# Outputs.net
KiCad netlist of a schematic drawn in Altium Designer
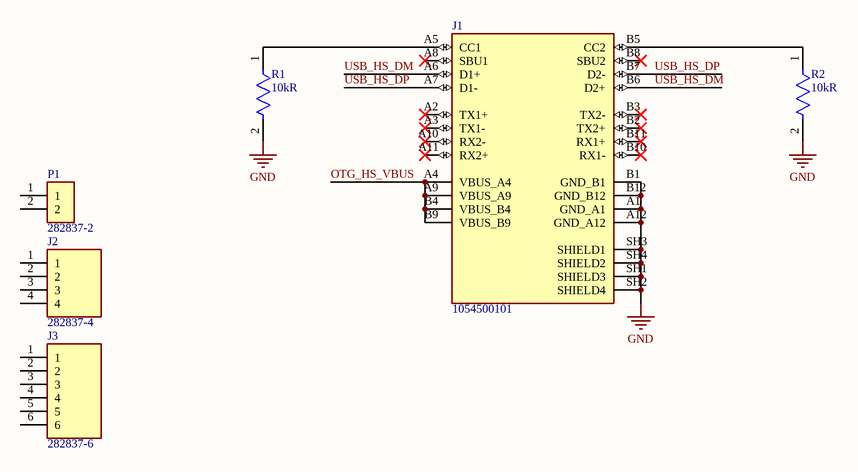
[diagram p0: Outputs.SchDoc]

(export (version "E")
  (design (tool "Eeschema 10.0.6"))
  (components
    (comp (ref "J1")
      (value "1054500101")
      (footprint "MOLEX_1054500101")
      (fields (field (name "MF") "Molex"))
      (libsource (lib "Erich Robb") (part "1054500101"))
    )
    (comp (ref "J2")
      (value "282837-4")
      (footprint "TE_282837-4")
      (description "4 Position Wire to Board Terminal Block Horizontal with Board 0.200 (5.08mm) Through Hole")
      (fields (field (name "MF") "TE Connectivity"))
      (libsource (lib "Erich Robb") (part "282837-4"))
    )
    (comp (ref "J3")
      (value "282837-6")
      (footprint "TE_282837-6")
      (description "Conn Terminal Block F 6 POS 5.08mm Solder ST Thru-Hole 13.5A/Contact")
      (fields (field (name "MF") "TE Connectivity"))
      (libsource (lib "Erich Robb") (part "282837-6"))
    )
    (comp (ref "P1")
      (value "282837-2")
      (footprint "TE_282837-2")
      (fields (field (name "MF") "TE Connectivity"))
      (libsource (lib "Erich Robb") (part "282837-2"))
    )
    (comp (ref "R1")
      (value "10kR")
      (footprint "FP-CPF0603-MFG")
      (description "RES SMD 2.15KΩ 0.1% 1/16W 0603")
      (fields
        (field (name "MANUFACTURER") "TE Connectivity")
        (field (name "OCTOPART") "https://octopart.com/cpf0603b2k15e1-te+connectivity-22739551")
      )
      (libsource (lib "Altium Content Vault") (part "1029c3af85768c4190bb7ad29bc67b5"))
    )
    (comp (ref "R2")
      (value "10kR")
      (footprint "FP-CPF0603-MFG")
      (description "RES SMD 2.15KΩ 0.1% 1/16W 0603")
      (fields
        (field (name "MANUFACTURER") "TE Connectivity")
        (field (name "OCTOPART") "https://octopart.com/cpf0603b2k15e1-te+connectivity-22739551")
      )
      (libsource (lib "Altium Content Vault") (part "1029c3af85768c4190bb7ad29bc67b5"))
    )
  )
  (nets
    (net (code "1") (name "/OTG_HS_VBUS") (class "Default")
      (node (ref "J1") (pin "A4") (pinfunction "VBUS_A4_A4") (pintype "power_in"))
      (node (ref "J1") (pin "A9") (pinfunction "VBUS_A9_A9") (pintype "power_in"))
      (node (ref "J1") (pin "B4") (pinfunction "VBUS_B4_B4") (pintype "power_in"))
      (node (ref "J1") (pin "B9") (pinfunction "VBUS_B9_B9") (pintype "power_in"))
    )
    (net (code "2") (name "/USB_HS_DM") (class "Default")
      (node (ref "J1") (pin "A6") (pinfunction "D1+_A6") (pintype "bidirectional"))
      (node (ref "J1") (pin "B6") (pinfunction "D2+_B6") (pintype "bidirectional"))
    )
    (net (code "3") (name "/USB_HS_DP") (class "Default")
      (node (ref "J1") (pin "A7") (pinfunction "D1-_A7") (pintype "bidirectional"))
      (node (ref "J1") (pin "B7") (pinfunction "D2-_B7") (pintype "bidirectional"))
    )
    (net (code "4") (name "GND") (class "Default")
      (node (ref "J1") (pin "A1") (pinfunction "GND_A1_A1") (pintype "power_in"))
      (node (ref "J1") (pin "A12") (pinfunction "GND_A12_A12") (pintype "power_in"))
      (node (ref "J1") (pin "B1") (pinfunction "GND_B1_B1") (pintype "power_in"))
      (node (ref "J1") (pin "B12") (pinfunction "GND_B12_B12") (pintype "power_in"))
      (node (ref "J1") (pin "SH1") (pinfunction "SHIELD3_SH1") (pintype "passive"))
      (node (ref "J1") (pin "SH2") (pinfunction "SHIELD4_SH2") (pintype "passive"))
      (node (ref "J1") (pin "SH3") (pinfunction "SHIELD1_SH3") (pintype "passive"))
      (node (ref "J1") (pin "SH4") (pinfunction "SHIELD2_SH4") (pintype "passive"))
      (node (ref "R1") (pin "2") (pinfunction "2_2") (pintype "passive"))
      (node (ref "R2") (pin "2") (pinfunction "2_2") (pintype "passive"))
    )
    (net (code "5") (name "Net-(J1-CC1)") (class "Default")
      (node (ref "J1") (pin "A5") (pinfunction "CC1_A5") (pintype "bidirectional"))
      (node (ref "R1") (pin "1") (pinfunction "1_1") (pintype "passive"))
    )
    (net (code "6") (name "Net-(J1-CC2)") (class "Default")
      (node (ref "J1") (pin "B5") (pinfunction "CC2_B5") (pintype "bidirectional"))
      (node (ref "R2") (pin "1") (pinfunction "1_1") (pintype "passive"))
    )
    (net (code "7") (name "unconnected-(J1-RX1+-PadB11)") (class "Default")
      (node (ref "J1") (pin "B11") (pinfunction "RX1+_B11") (pintype "bidirectional+no_connect"))
    )
    (net (code "8") (name "unconnected-(J1-RX1--PadB10)") (class "Default")
      (node (ref "J1") (pin "B10") (pinfunction "RX1-_B10") (pintype "bidirectional+no_connect"))
    )
    (net (code "9") (name "unconnected-(J1-RX2+-PadA11)") (class "Default")
      (node (ref "J1") (pin "A11") (pinfunction "RX2+_A11") (pintype "bidirectional+no_connect"))
    )
    (net (code "10") (name "unconnected-(J1-RX2--PadA10)") (class "Default")
      (node (ref "J1") (pin "A10") (pinfunction "RX2-_A10") (pintype "bidirectional+no_connect"))
    )
    (net (code "11") (name "unconnected-(J1-SBU1-PadA8)") (class "Default")
      (node (ref "J1") (pin "A8") (pinfunction "SBU1_A8") (pintype "bidirectional+no_connect"))
    )
    (net (code "12") (name "unconnected-(J1-SBU2-PadB8)") (class "Default")
      (node (ref "J1") (pin "B8") (pinfunction "SBU2_B8") (pintype "bidirectional+no_connect"))
    )
    (net (code "13") (name "unconnected-(J1-TX1+-PadA2)") (class "Default")
      (node (ref "J1") (pin "A2") (pinfunction "TX1+_A2") (pintype "bidirectional+no_connect"))
    )
    (net (code "14") (name "unconnected-(J1-TX1--PadA3)") (class "Default")
      (node (ref "J1") (pin "A3") (pinfunction "TX1-_A3") (pintype "bidirectional+no_connect"))
    )
    (net (code "15") (name "unconnected-(J1-TX2+-PadB2)") (class "Default")
      (node (ref "J1") (pin "B2") (pinfunction "TX2+_B2") (pintype "bidirectional+no_connect"))
    )
    (net (code "16") (name "unconnected-(J1-TX2--PadB3)") (class "Default")
      (node (ref "J1") (pin "B3") (pinfunction "TX2-_B3") (pintype "bidirectional+no_connect"))
    )
    (net (code "17") (name "unconnected-(J2-Pad1)") (class "Default")
      (node (ref "J2") (pin "1") (pinfunction "1_1") (pintype "passive"))
    )
    (net (code "18") (name "unconnected-(J2-Pad2)") (class "Default")
      (node (ref "J2") (pin "2") (pinfunction "2_2") (pintype "passive"))
    )
    (net (code "19") (name "unconnected-(J2-Pad3)") (class "Default")
      (node (ref "J2") (pin "3") (pinfunction "3_3") (pintype "passive"))
    )
    (net (code "20") (name "unconnected-(J2-Pad4)") (class "Default")
      (node (ref "J2") (pin "4") (pinfunction "4_4") (pintype "passive"))
    )
    (net (code "21") (name "unconnected-(J3-Pad1)") (class "Default")
      (node (ref "J3") (pin "1") (pinfunction "1_1") (pintype "passive"))
    )
    (net (code "22") (name "unconnected-(J3-Pad2)") (class "Default")
      (node (ref "J3") (pin "2") (pinfunction "2_2") (pintype "passive"))
    )
    (net (code "23") (name "unconnected-(J3-Pad3)") (class "Default")
      (node (ref "J3") (pin "3") (pinfunction "3_3") (pintype "passive"))
    )
    (net (code "24") (name "unconnected-(J3-Pad4)") (class "Default")
      (node (ref "J3") (pin "4") (pinfunction "4_4") (pintype "passive"))
    )
    (net (code "25") (name "unconnected-(J3-Pad5)") (class "Default")
      (node (ref "J3") (pin "5") (pinfunction "5_5") (pintype "passive"))
    )
    (net (code "26") (name "unconnected-(J3-Pad6)") (class "Default")
      (node (ref "J3") (pin "6") (pinfunction "6_6") (pintype "passive"))
    )
    (net (code "27") (name "unconnected-(P1-Pad1)") (class "Default")
      (node (ref "P1") (pin "1") (pinfunction "1_1") (pintype "passive"))
    )
    (net (code "28") (name "unconnected-(P1-Pad2)") (class "Default")
      (node (ref "P1") (pin "2") (pinfunction "2_2") (pintype "passive"))
    )
  )
)
